# RF08bck.net
KiCad netlist of a schematic drawn in EAGLE
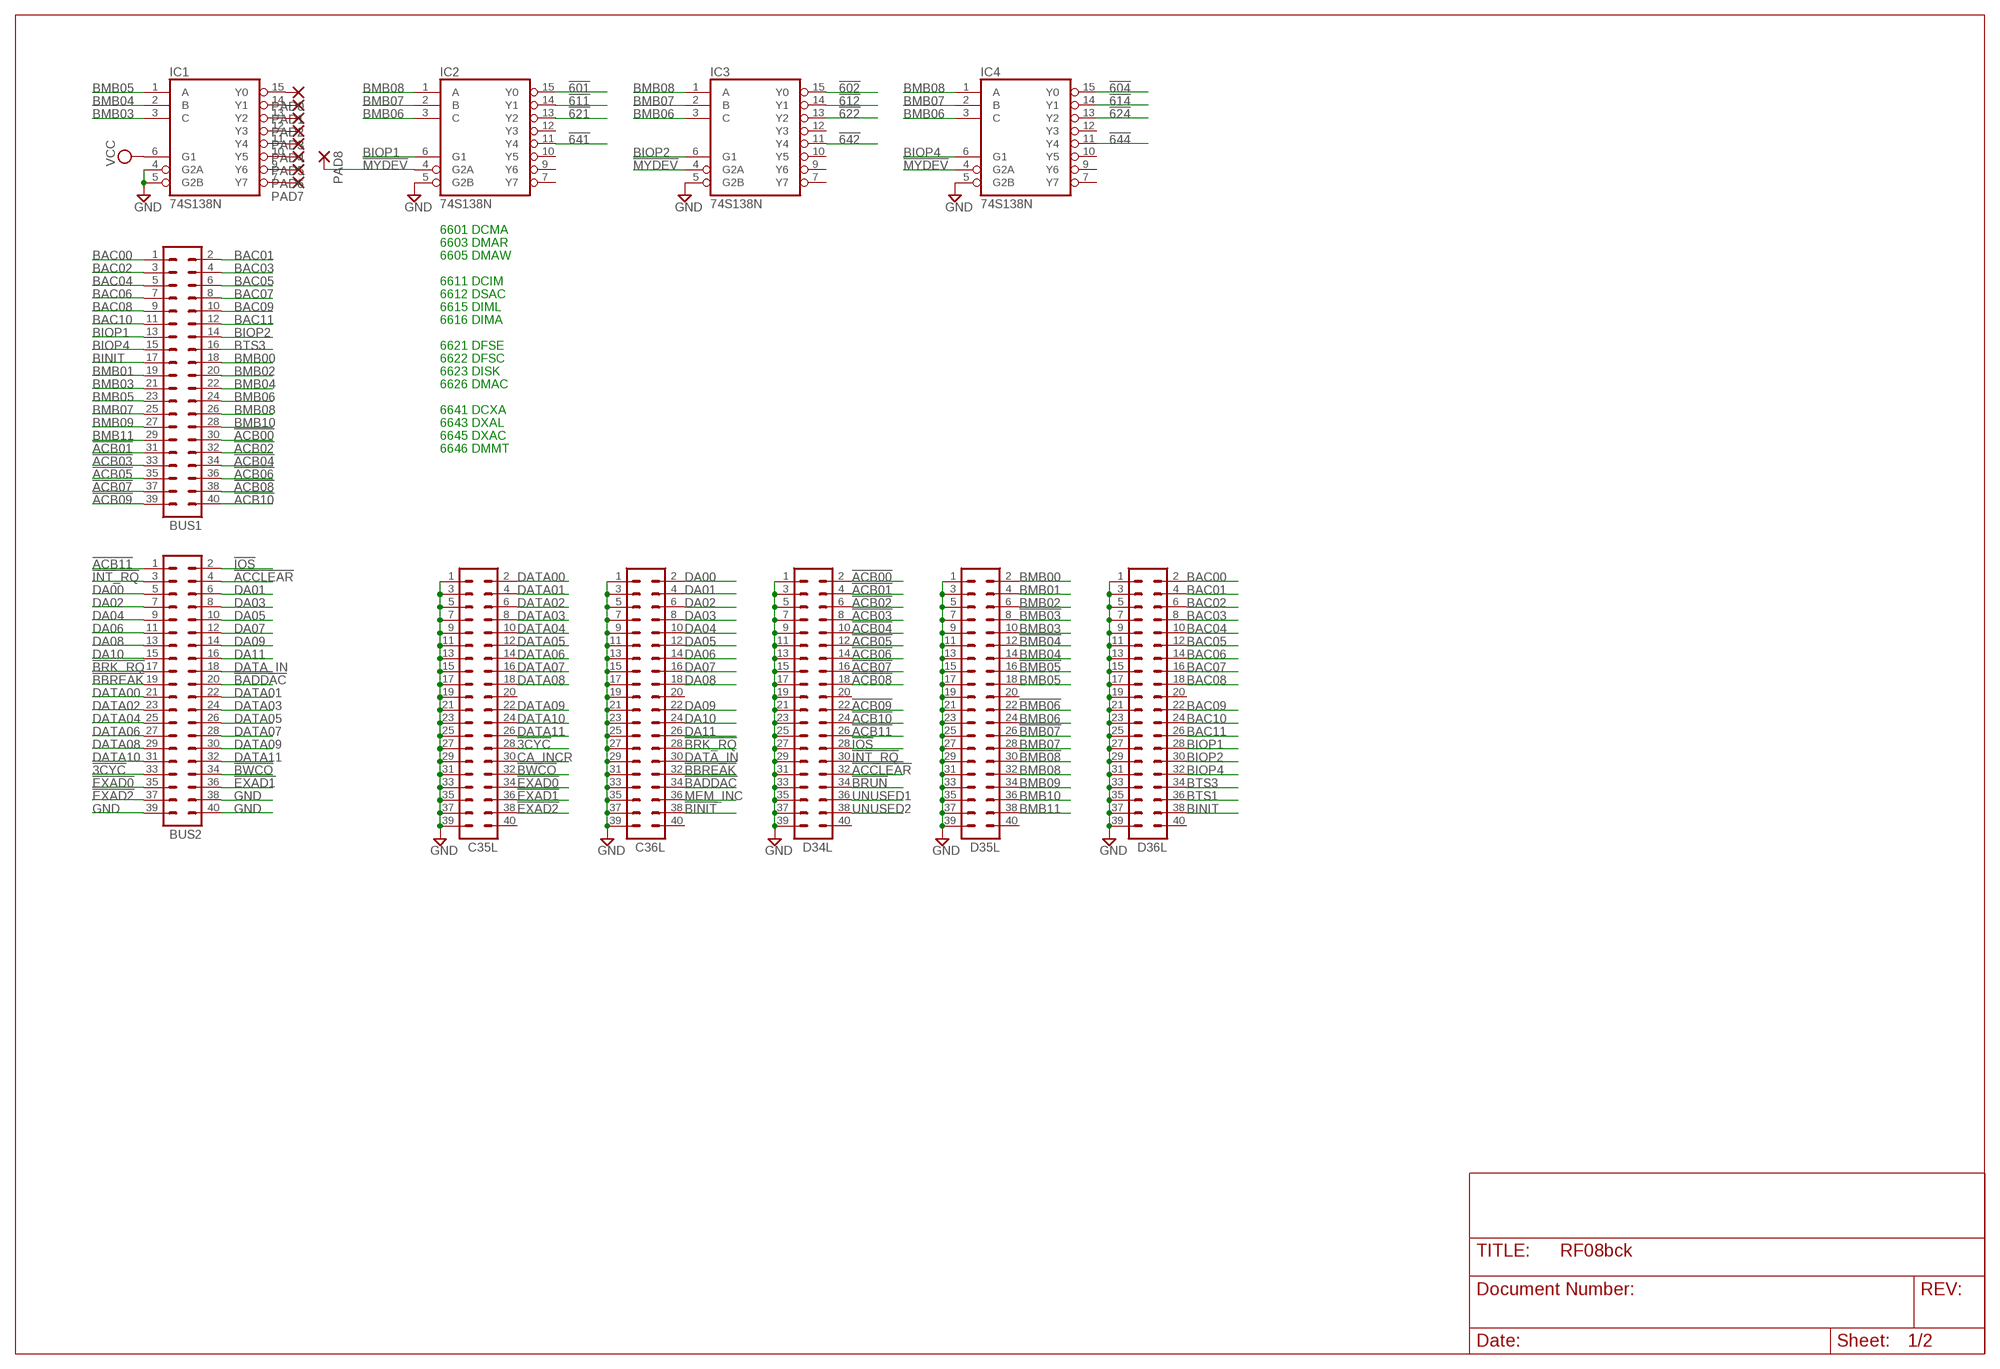
[diagram p0: schematic, sheet 1]
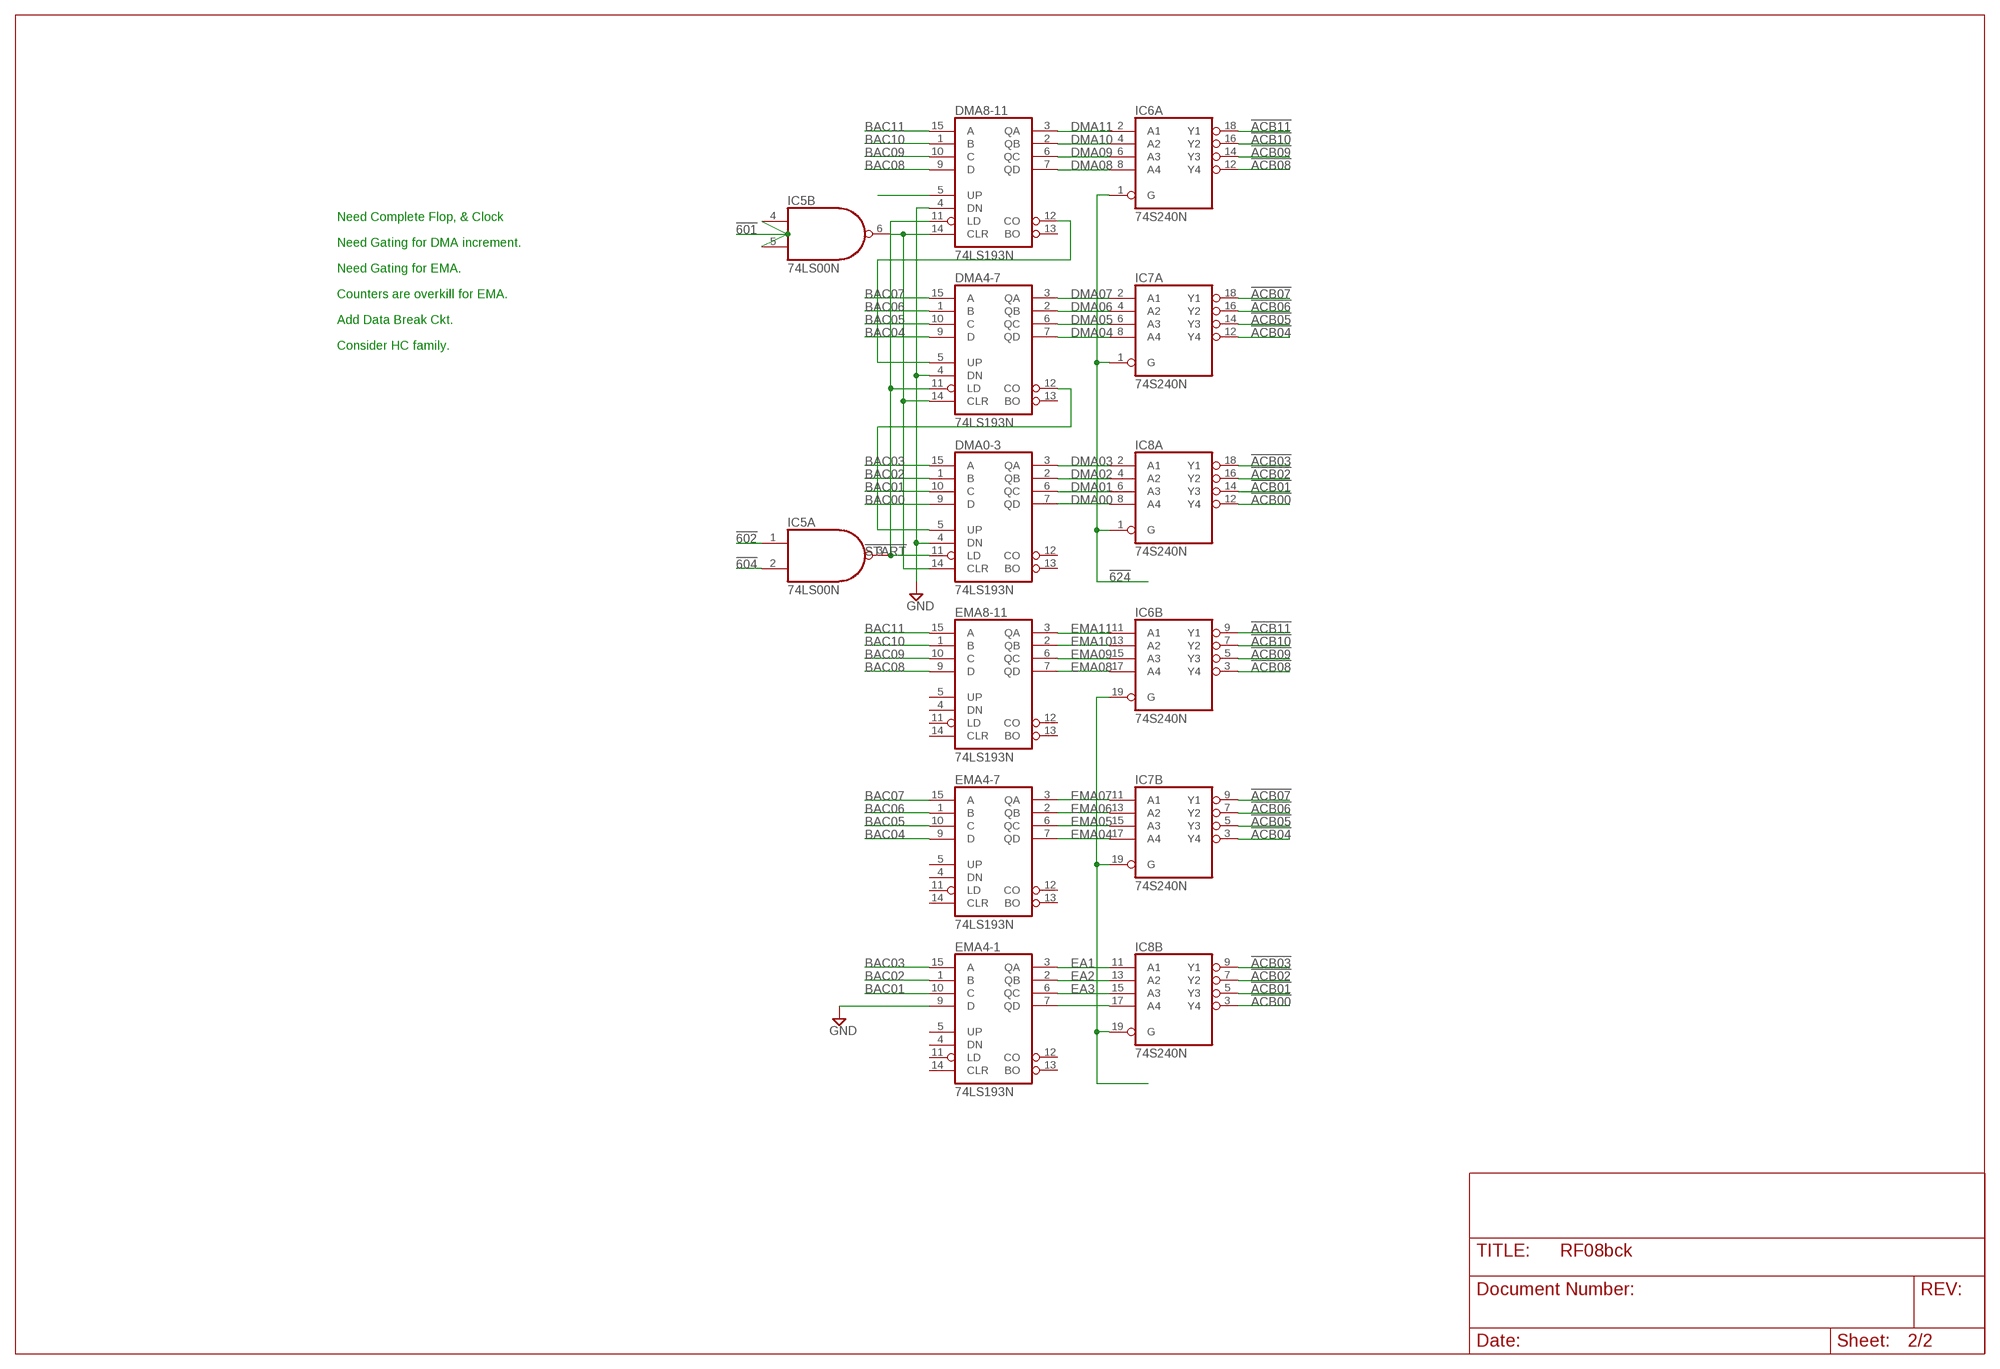
[diagram p1: schematic, sheet 2]

(export (version "E")
  (design (tool "Eeschema 10.0.6"))
  (components
    (comp (ref "DMA0-3")
      (value "74LS193N")
      (footprint "eagle-import:DIL16")
      (libsource (lib "eagle-import") (part "74192NLS"))
    )
    (comp (ref "DMA4-7")
      (value "74LS193N")
      (footprint "eagle-import:DIL16")
      (libsource (lib "eagle-import") (part "74192NLS"))
    )
    (comp (ref "DMA8-11")
      (value "74LS193N")
      (footprint "eagle-import:DIL16")
      (libsource (lib "eagle-import") (part "74192NLS"))
    )
    (comp (ref "EMA4-1")
      (value "74LS193N")
      (footprint "eagle-import:DIL16")
      (libsource (lib "eagle-import") (part "74192NLS"))
    )
    (comp (ref "EMA4-7")
      (value "74LS193N")
      (footprint "eagle-import:DIL16")
      (libsource (lib "eagle-import") (part "74192NLS"))
    )
    (comp (ref "EMA8-11")
      (value "74LS193N")
      (footprint "eagle-import:DIL16")
      (libsource (lib "eagle-import") (part "74192NLS"))
    )
    (comp (ref "IC5")
      (value "74LS00N")
      (footprint "eagle-import:DIL14")
      (libsource (lib "eagle-import") (part "7400NLS"))
    )
    (comp (ref "IC6")
      (value "74S240N")
      (footprint "eagle-import:DIL20")
      (libsource (lib "eagle-import") (part "74240NS"))
    )
    (comp (ref "IC7")
      (value "74S240N")
      (footprint "eagle-import:DIL20")
      (libsource (lib "eagle-import") (part "74240NS"))
    )
    (comp (ref "IC8")
      (value "74S240N")
      (footprint "eagle-import:DIL20")
      (libsource (lib "eagle-import") (part "74240NS"))
    )
    (comp (ref "BUS1")
      (value "MA20-2")
      (footprint "eagle-import:MA20-2")
      (libsource (lib "eagle-import") (part "MA20-2"))
    )
    (comp (ref "BUS2")
      (value "MA20-2")
      (footprint "eagle-import:MA20-2")
      (libsource (lib "eagle-import") (part "MA20-2"))
    )
    (comp (ref "C35L")
      (value "MA20-2")
      (footprint "eagle-import:MA20-2")
      (libsource (lib "eagle-import") (part "MA20-2"))
    )
    (comp (ref "C36L")
      (value "MA20-2")
      (footprint "eagle-import:MA20-2")
      (libsource (lib "eagle-import") (part "MA20-2"))
    )
    (comp (ref "D34L")
      (value "MA20-2")
      (footprint "eagle-import:MA20-2")
      (libsource (lib "eagle-import") (part "MA20-2"))
    )
    (comp (ref "D35L")
      (value "MA20-2")
      (footprint "eagle-import:MA20-2")
      (libsource (lib "eagle-import") (part "MA20-2"))
    )
    (comp (ref "D36L")
      (value "MA20-2")
      (footprint "eagle-import:MA20-2")
      (libsource (lib "eagle-import") (part "MA20-2"))
    )
    (comp (ref "IC1")
      (value "74S138N")
      (footprint "eagle-import:DIL16")
      (libsource (lib "eagle-import") (part "74138NS"))
    )
    (comp (ref "IC2")
      (value "74S138N")
      (footprint "eagle-import:DIL16")
      (libsource (lib "eagle-import") (part "74138NS"))
    )
    (comp (ref "IC3")
      (value "74S138N")
      (footprint "eagle-import:DIL16")
      (libsource (lib "eagle-import") (part "74138NS"))
    )
    (comp (ref "IC4")
      (value "74S138N")
      (footprint "eagle-import:DIL16")
      (libsource (lib "eagle-import") (part "74138NS"))
    )
    (comp (ref "PAD0")
      (value "1,6/0,8")
      (footprint "eagle-import:1,6_0,8")
      (libsource (lib "eagle-import") (part "1,6/0,8"))
    )
    (comp (ref "PAD1")
      (value "1,6/0,8")
      (footprint "eagle-import:1,6_0,8")
      (libsource (lib "eagle-import") (part "1,6/0,8"))
    )
    (comp (ref "PAD2")
      (value "1,6/0,8")
      (footprint "eagle-import:1,6_0,8")
      (libsource (lib "eagle-import") (part "1,6/0,8"))
    )
    (comp (ref "PAD3")
      (value "1,6/0,8")
      (footprint "eagle-import:1,6_0,8")
      (libsource (lib "eagle-import") (part "1,6/0,8"))
    )
    (comp (ref "PAD4")
      (value "1,6/0,8")
      (footprint "eagle-import:1,6_0,8")
      (libsource (lib "eagle-import") (part "1,6/0,8"))
    )
    (comp (ref "PAD5")
      (value "1,6/0,8")
      (footprint "eagle-import:1,6_0,8")
      (libsource (lib "eagle-import") (part "1,6/0,8"))
    )
    (comp (ref "PAD6")
      (value "1,6/0,8")
      (footprint "eagle-import:1,6_0,8")
      (libsource (lib "eagle-import") (part "1,6/0,8"))
    )
    (comp (ref "PAD7")
      (value "1,6/0,8")
      (footprint "eagle-import:1,6_0,8")
      (libsource (lib "eagle-import") (part "1,6/0,8"))
    )
    (comp (ref "PAD8")
      (value "1,6/0,8")
      (footprint "eagle-import:1,6_0,8")
      (libsource (lib "eagle-import") (part "1,6/0,8"))
    )
  )
  (nets
    (net (code "1") (name "BAC00") (class "Default")
      (node (ref "BUS1") (pin "1") (pinfunction "1_1") (pintype "passive"))
      (node (ref "D36L") (pin "2") (pinfunction "2_2") (pintype "passive"))
      (node (ref "DMA0-3") (pin "9") (pinfunction "D_9") (pintype "input"))
    )
    (net (code "2") (name "BAC01") (class "Default")
      (node (ref "BUS1") (pin "2") (pinfunction "2_2") (pintype "passive"))
      (node (ref "D36L") (pin "4") (pinfunction "4_4") (pintype "passive"))
      (node (ref "DMA0-3") (pin "10") (pinfunction "C_10") (pintype "input"))
      (node (ref "EMA4-1") (pin "10") (pinfunction "C_10") (pintype "input"))
    )
    (net (code "3") (name "BAC02") (class "Default")
      (node (ref "BUS1") (pin "3") (pinfunction "3_3") (pintype "passive"))
      (node (ref "D36L") (pin "6") (pinfunction "6_6") (pintype "passive"))
      (node (ref "DMA0-3") (pin "1") (pinfunction "B_1") (pintype "input"))
      (node (ref "EMA4-1") (pin "1") (pinfunction "B_1") (pintype "input"))
    )
    (net (code "4") (name "BAC03") (class "Default")
      (node (ref "BUS1") (pin "4") (pinfunction "4_4") (pintype "passive"))
      (node (ref "D36L") (pin "8") (pinfunction "8_8") (pintype "passive"))
      (node (ref "DMA0-3") (pin "15") (pinfunction "A_15") (pintype "input"))
      (node (ref "EMA4-1") (pin "15") (pinfunction "A_15") (pintype "input"))
    )
    (net (code "5") (name "BAC04") (class "Default")
      (node (ref "BUS1") (pin "5") (pinfunction "5_5") (pintype "passive"))
      (node (ref "D36L") (pin "10") (pinfunction "10_10") (pintype "passive"))
      (node (ref "DMA4-7") (pin "9") (pinfunction "D_9") (pintype "input"))
      (node (ref "EMA4-7") (pin "9") (pinfunction "D_9") (pintype "input"))
    )
    (net (code "6") (name "BAC05") (class "Default")
      (node (ref "BUS1") (pin "6") (pinfunction "6_6") (pintype "passive"))
      (node (ref "D36L") (pin "12") (pinfunction "12_12") (pintype "passive"))
      (node (ref "DMA4-7") (pin "10") (pinfunction "C_10") (pintype "input"))
      (node (ref "EMA4-7") (pin "10") (pinfunction "C_10") (pintype "input"))
    )
    (net (code "7") (name "BAC06") (class "Default")
      (node (ref "BUS1") (pin "7") (pinfunction "7_7") (pintype "passive"))
      (node (ref "D36L") (pin "14") (pinfunction "14_14") (pintype "passive"))
      (node (ref "DMA4-7") (pin "1") (pinfunction "B_1") (pintype "input"))
      (node (ref "EMA4-7") (pin "1") (pinfunction "B_1") (pintype "input"))
    )
    (net (code "8") (name "BAC07") (class "Default")
      (node (ref "BUS1") (pin "8") (pinfunction "8_8") (pintype "passive"))
      (node (ref "D36L") (pin "16") (pinfunction "16_16") (pintype "passive"))
      (node (ref "DMA4-7") (pin "15") (pinfunction "A_15") (pintype "input"))
      (node (ref "EMA4-7") (pin "15") (pinfunction "A_15") (pintype "input"))
    )
    (net (code "9") (name "BAC08") (class "Default")
      (node (ref "BUS1") (pin "9") (pinfunction "9_9") (pintype "passive"))
      (node (ref "D36L") (pin "18") (pinfunction "18_18") (pintype "passive"))
      (node (ref "DMA8-11") (pin "9") (pinfunction "D_9") (pintype "input"))
      (node (ref "EMA8-11") (pin "9") (pinfunction "D_9") (pintype "input"))
    )
    (net (code "10") (name "BAC09") (class "Default")
      (node (ref "BUS1") (pin "10") (pinfunction "10_10") (pintype "passive"))
      (node (ref "D36L") (pin "22") (pinfunction "22_22") (pintype "passive"))
      (node (ref "DMA8-11") (pin "10") (pinfunction "C_10") (pintype "input"))
      (node (ref "EMA8-11") (pin "10") (pinfunction "C_10") (pintype "input"))
    )
    (net (code "11") (name "BAC10") (class "Default")
      (node (ref "BUS1") (pin "11") (pinfunction "11_11") (pintype "passive"))
      (node (ref "D36L") (pin "24") (pinfunction "24_24") (pintype "passive"))
      (node (ref "DMA8-11") (pin "1") (pinfunction "B_1") (pintype "input"))
      (node (ref "EMA8-11") (pin "1") (pinfunction "B_1") (pintype "input"))
    )
    (net (code "12") (name "BAC11") (class "Default")
      (node (ref "BUS1") (pin "12") (pinfunction "12_12") (pintype "passive"))
      (node (ref "D36L") (pin "26") (pinfunction "26_26") (pintype "passive"))
      (node (ref "DMA8-11") (pin "15") (pinfunction "A_15") (pintype "input"))
      (node (ref "EMA8-11") (pin "15") (pinfunction "A_15") (pintype "input"))
    )
    (net (code "13") (name "BINIT") (class "Default")
      (node (ref "BUS1") (pin "17") (pinfunction "17_17") (pintype "passive"))
      (node (ref "D36L") (pin "38") (pinfunction "38_38") (pintype "passive"))
    )
    (net (code "14") (name "BIOP1") (class "Default")
      (node (ref "BUS1") (pin "13") (pinfunction "13_13") (pintype "passive"))
      (node (ref "D36L") (pin "28") (pinfunction "28_28") (pintype "passive"))
      (node (ref "IC2") (pin "6") (pinfunction "G1_6") (pintype "input"))
    )
    (net (code "15") (name "BIOP2") (class "Default")
      (node (ref "BUS1") (pin "14") (pinfunction "14_14") (pintype "passive"))
      (node (ref "D36L") (pin "30") (pinfunction "30_30") (pintype "passive"))
      (node (ref "IC3") (pin "6") (pinfunction "G1_6") (pintype "input"))
    )
    (net (code "16") (name "BIOP4") (class "Default")
      (node (ref "BUS1") (pin "15") (pinfunction "15_15") (pintype "passive"))
      (node (ref "D36L") (pin "32") (pinfunction "32_32") (pintype "passive"))
      (node (ref "IC4") (pin "6") (pinfunction "G1_6") (pintype "input"))
    )
    (net (code "17") (name "BMB00") (class "Default")
      (node (ref "BUS1") (pin "18") (pinfunction "18_18") (pintype "passive"))
      (node (ref "D35L") (pin "2") (pinfunction "2_2") (pintype "passive"))
    )
    (net (code "18") (name "BMB01") (class "Default")
      (node (ref "BUS1") (pin "19") (pinfunction "19_19") (pintype "passive"))
      (node (ref "D35L") (pin "4") (pinfunction "4_4") (pintype "passive"))
    )
    (net (code "19") (name "BMB02") (class "Default")
      (node (ref "BUS1") (pin "20") (pinfunction "20_20") (pintype "passive"))
      (node (ref "D35L") (pin "6") (pinfunction "6_6") (pintype "passive"))
    )
    (net (code "20") (name "BMB03") (class "Default")
      (node (ref "BUS1") (pin "21") (pinfunction "21_21") (pintype "passive"))
      (node (ref "D35L") (pin "10") (pinfunction "10_10") (pintype "passive"))
      (node (ref "IC1") (pin "3") (pinfunction "C_3") (pintype "input"))
    )
    (net (code "21") (name "BMB04") (class "Default")
      (node (ref "BUS1") (pin "22") (pinfunction "22_22") (pintype "passive"))
      (node (ref "D35L") (pin "14") (pinfunction "14_14") (pintype "passive"))
      (node (ref "IC1") (pin "2") (pinfunction "B_2") (pintype "input"))
    )
    (net (code "22") (name "BMB05") (class "Default")
      (node (ref "BUS1") (pin "23") (pinfunction "23_23") (pintype "passive"))
      (node (ref "D35L") (pin "18") (pinfunction "18_18") (pintype "passive"))
      (node (ref "IC1") (pin "1") (pinfunction "A_1") (pintype "input"))
    )
    (net (code "23") (name "BMB06") (class "Default")
      (node (ref "BUS1") (pin "24") (pinfunction "24_24") (pintype "passive"))
      (node (ref "D35L") (pin "24") (pinfunction "24_24") (pintype "passive"))
      (node (ref "IC2") (pin "3") (pinfunction "C_3") (pintype "input"))
      (node (ref "IC3") (pin "3") (pinfunction "C_3") (pintype "input"))
      (node (ref "IC4") (pin "3") (pinfunction "C_3") (pintype "input"))
    )
    (net (code "24") (name "BMB07") (class "Default")
      (node (ref "BUS1") (pin "25") (pinfunction "25_25") (pintype "passive"))
      (node (ref "D35L") (pin "28") (pinfunction "28_28") (pintype "passive"))
      (node (ref "IC2") (pin "2") (pinfunction "B_2") (pintype "input"))
      (node (ref "IC3") (pin "2") (pinfunction "B_2") (pintype "input"))
      (node (ref "IC4") (pin "2") (pinfunction "B_2") (pintype "input"))
    )
    (net (code "25") (name "BMB08") (class "Default")
      (node (ref "BUS1") (pin "26") (pinfunction "26_26") (pintype "passive"))
      (node (ref "D35L") (pin "32") (pinfunction "32_32") (pintype "passive"))
      (node (ref "IC2") (pin "1") (pinfunction "A_1") (pintype "input"))
      (node (ref "IC3") (pin "1") (pinfunction "A_1") (pintype "input"))
      (node (ref "IC4") (pin "1") (pinfunction "A_1") (pintype "input"))
    )
    (net (code "26") (name "BMB09") (class "Default")
      (node (ref "BUS1") (pin "27") (pinfunction "27_27") (pintype "passive"))
      (node (ref "D35L") (pin "34") (pinfunction "34_34") (pintype "passive"))
    )
    (net (code "27") (name "BMB10") (class "Default")
      (node (ref "BUS1") (pin "28") (pinfunction "28_28") (pintype "passive"))
      (node (ref "D35L") (pin "36") (pinfunction "36_36") (pintype "passive"))
    )
    (net (code "28") (name "BMB11") (class "Default")
      (node (ref "BUS1") (pin "29") (pinfunction "29_29") (pintype "passive"))
      (node (ref "D35L") (pin "38") (pinfunction "38_38") (pintype "passive"))
    )
    (net (code "29") (name "BTS1") (class "Default")
      (node (ref "D36L") (pin "36") (pinfunction "36_36") (pintype "passive"))
    )
    (net (code "30") (name "BTS3") (class "Default")
      (node (ref "BUS1") (pin "16") (pinfunction "16_16") (pintype "passive"))
      (node (ref "D36L") (pin "34") (pinfunction "34_34") (pintype "passive"))
    )
    (net (code "31") (name "CA_INCR") (class "Default")
      (node (ref "C35L") (pin "30") (pinfunction "30_30") (pintype "passive"))
    )
    (net (code "32") (name "DA00") (class "Default")
      (node (ref "BUS2") (pin "5") (pinfunction "5_5") (pintype "passive"))
      (node (ref "C36L") (pin "2") (pinfunction "2_2") (pintype "passive"))
    )
    (net (code "33") (name "DA01") (class "Default")
      (node (ref "BUS2") (pin "6") (pinfunction "6_6") (pintype "passive"))
      (node (ref "C36L") (pin "4") (pinfunction "4_4") (pintype "passive"))
    )
    (net (code "34") (name "DA02") (class "Default")
      (node (ref "BUS2") (pin "7") (pinfunction "7_7") (pintype "passive"))
      (node (ref "C36L") (pin "6") (pinfunction "6_6") (pintype "passive"))
    )
    (net (code "35") (name "DA03") (class "Default")
      (node (ref "BUS2") (pin "8") (pinfunction "8_8") (pintype "passive"))
      (node (ref "C36L") (pin "8") (pinfunction "8_8") (pintype "passive"))
    )
    (net (code "36") (name "DA04") (class "Default")
      (node (ref "BUS2") (pin "9") (pinfunction "9_9") (pintype "passive"))
      (node (ref "C36L") (pin "10") (pinfunction "10_10") (pintype "passive"))
    )
    (net (code "37") (name "DA05") (class "Default")
      (node (ref "BUS2") (pin "10") (pinfunction "10_10") (pintype "passive"))
      (node (ref "C36L") (pin "12") (pinfunction "12_12") (pintype "passive"))
    )
    (net (code "38") (name "DA06") (class "Default")
      (node (ref "BUS2") (pin "11") (pinfunction "11_11") (pintype "passive"))
      (node (ref "C36L") (pin "14") (pinfunction "14_14") (pintype "passive"))
    )
    (net (code "39") (name "DA07") (class "Default")
      (node (ref "BUS2") (pin "12") (pinfunction "12_12") (pintype "passive"))
      (node (ref "C36L") (pin "16") (pinfunction "16_16") (pintype "passive"))
    )
    (net (code "40") (name "DA08") (class "Default")
      (node (ref "BUS2") (pin "13") (pinfunction "13_13") (pintype "passive"))
      (node (ref "C36L") (pin "18") (pinfunction "18_18") (pintype "passive"))
    )
    (net (code "41") (name "DA09") (class "Default")
      (node (ref "BUS2") (pin "14") (pinfunction "14_14") (pintype "passive"))
      (node (ref "C36L") (pin "22") (pinfunction "22_22") (pintype "passive"))
    )
    (net (code "42") (name "DA10") (class "Default")
      (node (ref "BUS2") (pin "15") (pinfunction "15_15") (pintype "passive"))
      (node (ref "C36L") (pin "24") (pinfunction "24_24") (pintype "passive"))
    )
    (net (code "43") (name "DA11") (class "Default")
      (node (ref "BUS2") (pin "16") (pinfunction "16_16") (pintype "passive"))
      (node (ref "C36L") (pin "26") (pinfunction "26_26") (pintype "passive"))
    )
    (net (code "44") (name "DATA00") (class "Default")
      (node (ref "BUS2") (pin "21") (pinfunction "21_21") (pintype "passive"))
      (node (ref "C35L") (pin "2") (pinfunction "2_2") (pintype "passive"))
    )
    (net (code "45") (name "DATA01") (class "Default")
      (node (ref "BUS2") (pin "22") (pinfunction "22_22") (pintype "passive"))
      (node (ref "C35L") (pin "4") (pinfunction "4_4") (pintype "passive"))
    )
    (net (code "46") (name "DATA02") (class "Default")
      (node (ref "BUS2") (pin "23") (pinfunction "23_23") (pintype "passive"))
      (node (ref "C35L") (pin "6") (pinfunction "6_6") (pintype "passive"))
    )
    (net (code "47") (name "DATA03") (class "Default")
      (node (ref "BUS2") (pin "24") (pinfunction "24_24") (pintype "passive"))
      (node (ref "C35L") (pin "8") (pinfunction "8_8") (pintype "passive"))
    )
    (net (code "48") (name "DATA04") (class "Default")
      (node (ref "BUS2") (pin "25") (pinfunction "25_25") (pintype "passive"))
      (node (ref "C35L") (pin "10") (pinfunction "10_10") (pintype "passive"))
    )
    (net (code "49") (name "DATA05") (class "Default")
      (node (ref "BUS2") (pin "26") (pinfunction "26_26") (pintype "passive"))
      (node (ref "C35L") (pin "12") (pinfunction "12_12") (pintype "passive"))
    )
    (net (code "50") (name "DATA06") (class "Default")
      (node (ref "BUS2") (pin "27") (pinfunction "27_27") (pintype "passive"))
      (node (ref "C35L") (pin "14") (pinfunction "14_14") (pintype "passive"))
    )
    (net (code "51") (name "DATA07") (class "Default")
      (node (ref "BUS2") (pin "28") (pinfunction "28_28") (pintype "passive"))
      (node (ref "C35L") (pin "16") (pinfunction "16_16") (pintype "passive"))
    )
    (net (code "52") (name "DATA08") (class "Default")
      (node (ref "BUS2") (pin "29") (pinfunction "29_29") (pintype "passive"))
      (node (ref "C35L") (pin "18") (pinfunction "18_18") (pintype "passive"))
    )
    (net (code "53") (name "DATA09") (class "Default")
      (node (ref "BUS2") (pin "30") (pinfunction "30_30") (pintype "passive"))
      (node (ref "C35L") (pin "22") (pinfunction "22_22") (pintype "passive"))
    )
    (net (code "54") (name "DATA10") (class "Default")
      (node (ref "BUS2") (pin "31") (pinfunction "31_31") (pintype "passive"))
      (node (ref "C35L") (pin "24") (pinfunction "24_24") (pintype "passive"))
    )
    (net (code "55") (name "DATA11") (class "Default")
      (node (ref "BUS2") (pin "32") (pinfunction "32_32") (pintype "passive"))
      (node (ref "C35L") (pin "26") (pinfunction "26_26") (pintype "passive"))
    )
    (net (code "56") (name "DATA_IN") (class "Default")
      (node (ref "BUS2") (pin "18") (pinfunction "18_18") (pintype "passive"))
      (node (ref "C36L") (pin "30") (pinfunction "30_30") (pintype "passive"))
    )
    (net (code "57") (name "DMA00") (class "Default")
      (node (ref "DMA0-3") (pin "7") (pinfunction "QD_7") (pintype "output"))
      (node (ref "IC8") (pin "8") (pinfunction "A4_8") (pintype "input"))
    )
    (net (code "58") (name "DMA01") (class "Default")
      (node (ref "DMA0-3") (pin "6") (pinfunction "QC_6") (pintype "output"))
      (node (ref "IC8") (pin "6") (pinfunction "A3_6") (pintype "input"))
    )
    (net (code "59") (name "DMA02") (class "Default")
      (node (ref "DMA0-3") (pin "2") (pinfunction "QB_2") (pintype "output"))
      (node (ref "IC8") (pin "4") (pinfunction "A2_4") (pintype "input"))
    )
    (net (code "60") (name "DMA03") (class "Default")
      (node (ref "DMA0-3") (pin "3") (pinfunction "QA_3") (pintype "output"))
      (node (ref "IC8") (pin "2") (pinfunction "A1_2") (pintype "input"))
    )
    (net (code "61") (name "DMA04") (class "Default")
      (node (ref "DMA4-7") (pin "7") (pinfunction "QD_7") (pintype "output"))
      (node (ref "IC7") (pin "8") (pinfunction "A4_8") (pintype "input"))
    )
    (net (code "62") (name "DMA05") (class "Default")
      (node (ref "DMA4-7") (pin "6") (pinfunction "QC_6") (pintype "output"))
      (node (ref "IC7") (pin "6") (pinfunction "A3_6") (pintype "input"))
    )
    (net (code "63") (name "DMA06") (class "Default")
      (node (ref "DMA4-7") (pin "2") (pinfunction "QB_2") (pintype "output"))
      (node (ref "IC7") (pin "4") (pinfunction "A2_4") (pintype "input"))
    )
    (net (code "64") (name "DMA07") (class "Default")
      (node (ref "DMA4-7") (pin "3") (pinfunction "QA_3") (pintype "output"))
      (node (ref "IC7") (pin "2") (pinfunction "A1_2") (pintype "input"))
    )
    (net (code "65") (name "DMA08") (class "Default")
      (node (ref "DMA8-11") (pin "7") (pinfunction "QD_7") (pintype "output"))
      (node (ref "IC6") (pin "8") (pinfunction "A4_8") (pintype "input"))
    )
    (net (code "66") (name "DMA09") (class "Default")
      (node (ref "DMA8-11") (pin "6") (pinfunction "QC_6") (pintype "output"))
      (node (ref "IC6") (pin "6") (pinfunction "A3_6") (pintype "input"))
    )
    (net (code "67") (name "DMA10") (class "Default")
      (node (ref "DMA8-11") (pin "2") (pinfunction "QB_2") (pintype "output"))
      (node (ref "IC6") (pin "4") (pinfunction "A2_4") (pintype "input"))
    )
    (net (code "68") (name "DMA11") (class "Default")
      (node (ref "DMA8-11") (pin "3") (pinfunction "QA_3") (pintype "output"))
      (node (ref "IC6") (pin "2") (pinfunction "A1_2") (pintype "input"))
    )
    (net (code "69") (name "EA1") (class "Default")
      (node (ref "EMA4-1") (pin "3") (pinfunction "QA_3") (pintype "output"))
      (node (ref "IC8") (pin "11") (pinfunction "A1_11") (pintype "input"))
    )
    (net (code "70") (name "EA2") (class "Default")
      (node (ref "EMA4-1") (pin "2") (pinfunction "QB_2") (pintype "output"))
      (node (ref "IC8") (pin "13") (pinfunction "A2_13") (pintype "input"))
    )
    (net (code "71") (name "EA3") (class "Default")
      (node (ref "EMA4-1") (pin "6") (pinfunction "QC_6") (pintype "output"))
      (node (ref "IC8") (pin "15") (pinfunction "A3_15") (pintype "input"))
    )
    (net (code "72") (name "EMA04") (class "Default")
      (node (ref "EMA4-7") (pin "7") (pinfunction "QD_7") (pintype "output"))
      (node (ref "IC7") (pin "17") (pinfunction "A4_17") (pintype "input"))
    )
    (net (code "73") (name "EMA05") (class "Default")
      (node (ref "EMA4-7") (pin "6") (pinfunction "QC_6") (pintype "output"))
      (node (ref "IC7") (pin "15") (pinfunction "A3_15") (pintype "input"))
    )
    (net (code "74") (name "EMA06") (class "Default")
      (node (ref "EMA4-7") (pin "2") (pinfunction "QB_2") (pintype "output"))
      (node (ref "IC7") (pin "13") (pinfunction "A2_13") (pintype "input"))
    )
    (net (code "75") (name "EMA07") (class "Default")
      (node (ref "EMA4-7") (pin "3") (pinfunction "QA_3") (pintype "output"))
      (node (ref "IC7") (pin "11") (pinfunction "A1_11") (pintype "input"))
    )
    (net (code "76") (name "EMA08") (class "Default")
      (node (ref "EMA8-11") (pin "7") (pinfunction "QD_7") (pintype "output"))
      (node (ref "IC6") (pin "17") (pinfunction "A4_17") (pintype "input"))
    )
    (net (code "77") (name "EMA09") (class "Default")
      (node (ref "EMA8-11") (pin "6") (pinfunction "QC_6") (pintype "output"))
      (node (ref "IC6") (pin "15") (pinfunction "A3_15") (pintype "input"))
    )
    (net (code "78") (name "EMA10") (class "Default")
      (node (ref "EMA8-11") (pin "2") (pinfunction "QB_2") (pintype "output"))
      (node (ref "IC6") (pin "13") (pinfunction "A2_13") (pintype "input"))
    )
    (net (code "79") (name "EMA11") (class "Default")
      (node (ref "EMA8-11") (pin "3") (pinfunction "QA_3") (pintype "output"))
      (node (ref "IC6") (pin "11") (pinfunction "A1_11") (pintype "input"))
    )
    (net (code "80") (name "GND") (class "Default")
      (node (ref "BUS2") (pin "38") (pinfunction "38_38") (pintype "passive"))
      (node (ref "BUS2") (pin "39") (pinfunction "39_39") (pintype "passive"))
      (node (ref "BUS2") (pin "40") (pinfunction "40_40") (pintype "passive"))
      (node (ref "C35L") (pin "1") (pinfunction "1_1") (pintype "passive"))
      (node (ref "C35L") (pin "11") (pinfunction "11_11") (pintype "passive"))
      (node (ref "C35L") (pin "13") (pinfunction "13_13") (pintype "passive"))
      (node (ref "C35L") (pin "15") (pinfunction "15_15") (pintype "passive"))
      (node (ref "C35L") (pin "17") (pinfunction "17_17") (pintype "passive"))
      (node (ref "C35L") (pin "19") (pinfunction "19_19") (pintype "passive"))
      (node (ref "C35L") (pin "21") (pinfunction "21_21") (pintype "passive"))
      (node (ref "C35L") (pin "23") (pinfunction "23_23") (pintype "passive"))
      (node (ref "C35L") (pin "25") (pinfunction "25_25") (pintype "passive"))
      (node (ref "C35L") (pin "27") (pinfunction "27_27") (pintype "passive"))
      (node (ref "C35L") (pin "29") (pinfunction "29_29") (pintype "passive"))
      (node (ref "C35L") (pin "3") (pinfunction "3_3") (pintype "passive"))
      (node (ref "C35L") (pin "31") (pinfunction "31_31") (pintype "passive"))
      (node (ref "C35L") (pin "33") (pinfunction "33_33") (pintype "passive"))
      (node (ref "C35L") (pin "35") (pinfunction "35_35") (pintype "passive"))
      (node (ref "C35L") (pin "37") (pinfunction "37_37") (pintype "passive"))
      (node (ref "C35L") (pin "39") (pinfunction "39_39") (pintype "passive"))
      (node (ref "C35L") (pin "5") (pinfunction "5_5") (pintype "passive"))
      (node (ref "C35L") (pin "7") (pinfunction "7_7") (pintype "passive"))
      (node (ref "C35L") (pin "9") (pinfunction "9_9") (pintype "passive"))
      (node (ref "C36L") (pin "1") (pinfunction "1_1") (pintype "passive"))
      (node (ref "C36L") (pin "11") (pinfunction "11_11") (pintype "passive"))
      (node (ref "C36L") (pin "13") (pinfunction "13_13") (pintype "passive"))
      (node (ref "C36L") (pin "15") (pinfunction "15_15") (pintype "passive"))
      (node (ref "C36L") (pin "17") (pinfunction "17_17") (pintype "passive"))
      (node (ref "C36L") (pin "19") (pinfunction "19_19") (pintype "passive"))
      (node (ref "C36L") (pin "21") (pinfunction "21_21") (pintype "passive"))
      (node (ref "C36L") (pin "23") (pinfunction "23_23") (pintype "passive"))
      (node (ref "C36L") (pin "25") (pinfunction "25_25") (pintype "passive"))
      (node (ref "C36L") (pin "27") (pinfunction "27_27") (pintype "passive"))
      (node (ref "C36L") (pin "29") (pinfunction "29_29") (pintype "passive"))
      (node (ref "C36L") (pin "3") (pinfunction "3_3") (pintype "passive"))
      (node (ref "C36L") (pin "31") (pinfunction "31_31") (pintype "passive"))
      (node (ref "C36L") (pin "33") (pinfunction "33_33") (pintype "passive"))
      (node (ref "C36L") (pin "35") (pinfunction "35_35") (pintype "passive"))
      (node (ref "C36L") (pin "37") (pinfunction "37_37") (pintype "passive"))
      (node (ref "C36L") (pin "39") (pinfunction "39_39") (pintype "passive"))
      (node (ref "C36L") (pin "5") (pinfunction "5_5") (pintype "passive"))
      (node (ref "C36L") (pin "7") (pinfunction "7_7") (pintype "passive"))
      (node (ref "C36L") (pin "9") (pinfunction "9_9") (pintype "passive"))
      (node (ref "D34L") (pin "1") (pinfunction "1_1") (pintype "passive"))
      (node (ref "D34L") (pin "11") (pinfunction "11_11") (pintype "passive"))
      (node (ref "D34L") (pin "13") (pinfunction "13_13") (pintype "passive"))
      (node (ref "D34L") (pin "15") (pinfunction "15_15") (pintype "passive"))
      (node (ref "D34L") (pin "17") (pinfunction "17_17") (pintype "passive"))
      (node (ref "D34L") (pin "19") (pinfunction "19_19") (pintype "passive"))
      (node (ref "D34L") (pin "21") (pinfunction "21_21") (pintype "passive"))
      (node (ref "D34L") (pin "23") (pinfunction "23_23") (pintype "passive"))
      (node (ref "D34L") (pin "25") (pinfunction "25_25") (pintype "passive"))
      (node (ref "D34L") (pin "27") (pinfunction "27_27") (pintype "passive"))
      (node (ref "D34L") (pin "29") (pinfunction "29_29") (pintype "passive"))
      (node (ref "D34L") (pin "3") (pinfunction "3_3") (pintype "passive"))
      (node (ref "D34L") (pin "31") (pinfunction "31_31") (pintype "passive"))
      (node (ref "D34L") (pin "33") (pinfunction "33_33") (pintype "passive"))
      (node (ref "D34L") (pin "35") (pinfunction "35_35") (pintype "passive"))
      (node (ref "D34L") (pin "37") (pinfunction "37_37") (pintype "passive"))
      (node (ref "D34L") (pin "39") (pinfunction "39_39") (pintype "passive"))
      (node (ref "D34L") (pin "5") (pinfunction "5_5") (pintype "passive"))
      (node (ref "D34L") (pin "7") (pinfunction "7_7") (pintype "passive"))
      (node (ref "D34L") (pin "9") (pinfunction "9_9") (pintype "passive"))
      (node (ref "D35L") (pin "1") (pinfunction "1_1") (pintype "passive"))
      (node (ref "D35L") (pin "11") (pinfunction "11_11") (pintype "passive"))
      (node (ref "D35L") (pin "13") (pinfunction "13_13") (pintype "passive"))
      (node (ref "D35L") (pin "15") (pinfunction "15_15") (pintype "passive"))
      (node (ref "D35L") (pin "17") (pinfunction "17_17") (pintype "passive"))
      (node (ref "D35L") (pin "19") (pinfunction "19_19") (pintype "passive"))
      (node (ref "D35L") (pin "21") (pinfunction "21_21") (pintype "passive"))
      (node (ref "D35L") (pin "23") (pinfunction "23_23") (pintype "passive"))
      (node (ref "D35L") (pin "25") (pinfunction "25_25") (pintype "passive"))
      (node (ref "D35L") (pin "27") (pinfunction "27_27") (pintype "passive"))
      (node (ref "D35L") (pin "29") (pinfunction "29_29") (pintype "passive"))
      (node (ref "D35L") (pin "3") (pinfunction "3_3") (pintype "passive"))
      (node (ref "D35L") (pin "31") (pinfunction "31_31") (pintype "passive"))
      (node (ref "D35L") (pin "33") (pinfunction "33_33") (pintype "passive"))
      (node (ref "D35L") (pin "35") (pinfunction "35_35") (pintype "passive"))
      (node (ref "D35L") (pin "37") (pinfunction "37_37") (pintype "passive"))
      (node (ref "D35L") (pin "39") (pinfunction "39_39") (pintype "passive"))
      (node (ref "D35L") (pin "5") (pinfunction "5_5") (pintype "passive"))
      (node (ref "D35L") (pin "7") (pinfunction "7_7") (pintype "passive"))
      (node (ref "D35L") (pin "9") (pinfunction "9_9") (pintype "passive"))
      (node (ref "D36L") (pin "1") (pinfunction "1_1") (pintype "passive"))
      (node (ref "D36L") (pin "11") (pinfunction "11_11") (pintype "passive"))
      (node (ref "D36L") (pin "13") (pinfunction "13_13") (pintype "passive"))
      (node (ref "D36L") (pin "15") (pinfunction "15_15") (pintype "passive"))
      (node (ref "D36L") (pin "17") (pinfunction "17_17") (pintype "passive"))
      (node (ref "D36L") (pin "19") (pinfunction "19_19") (pintype "passive"))
      (node (ref "D36L") (pin "21") (pinfunction "21_21") (pintype "passive"))
      (node (ref "D36L") (pin "23") (pinfunction "23_23") (pintype "passive"))
      (node (ref "D36L") (pin "25") (pinfunction "25_25") (pintype "passive"))
      (node (ref "D36L") (pin "27") (pinfunction "27_27") (pintype "passive"))
      (node (ref "D36L") (pin "29") (pinfunction "29_29") (pintype "passive"))
      (node (ref "D36L") (pin "3") (pinfunction "3_3") (pintype "passive"))
      (node (ref "D36L") (pin "31") (pinfunction "31_31") (pintype "passive"))
      (node (ref "D36L") (pin "33") (pinfunction "33_33") (pintype "passive"))
      (node (ref "D36L") (pin "35") (pinfunction "35_35") (pintype "passive"))
      (node (ref "D36L") (pin "37") (pinfunction "37_37") (pintype "passive"))
      (node (ref "D36L") (pin "39") (pinfunction "39_39") (pintype "passive"))
      (node (ref "D36L") (pin "5") (pinfunction "5_5") (pintype "passive"))
      (node (ref "D36L") (pin "7") (pinfunction "7_7") (pintype "passive"))
      (node (ref "D36L") (pin "9") (pinfunction "9_9") (pintype "passive"))
      (node (ref "DMA0-3") (pin "4") (pinfunction "DN_4") (pintype "input"))
      (node (ref "DMA4-7") (pin "4") (pinfunction "DN_4") (pintype "input"))
      (node (ref "DMA8-11") (pin "4") (pinfunction "DN_4") (pintype "input"))
      (node (ref "EMA4-1") (pin "9") (pinfunction "D_9") (pintype "input"))
      (node (ref "IC1") (pin "4") (pinfunction "G2A_4") (pintype "input"))
      (node (ref "IC1") (pin "5") (pinfunction "G2B_5") (pintype "input"))
      (node (ref "IC2") (pin "5") (pinfunction "G2B_5") (pintype "input"))
      (node (ref "IC3") (pin "5") (pinfunction "G2B_5") (pintype "input"))
      (node (ref "IC4") (pin "5") (pinfunction "G2B_5") (pintype "input"))
    )
    (net (code "81") (name "MEM_INC") (class "Default")
      (node (ref "C36L") (pin "36") (pinfunction "36_36") (pintype "passive"))
    )
    (net (code "82") (name "Net-(DMA0-3A-CLR)") (class "Default")
      (node (ref "DMA0-3") (pin "14") (pinfunction "CLR_14") (pintype "input"))
      (node (ref "DMA4-7") (pin "14") (pinfunction "CLR_14") (pintype "input"))
      (node (ref "DMA8-11") (pin "14") (pinfunction "CLR_14") (pintype "input"))
      (node (ref "IC5") (pin "6") (pinfunction "O_6") (pintype "output"))
    )
    (net (code "83") (name "Net-(DMA0-3A-UP)") (class "Default")
      (node (ref "DMA0-3") (pin "5") (pinfunction "UP_5") (pintype "input"))
      (node (ref "DMA4-7") (pin "12") (pinfunction "CO_12") (pintype "output"))
    )
    (net (code "84") (name "Net-(DMA4-7A-UP)") (class "Default")
      (node (ref "DMA4-7") (pin "5") (pinfunction "UP_5") (pintype "input"))
      (node (ref "DMA8-11") (pin "12") (pinfunction "CO_12") (pintype "output"))
    )
    (net (code "85") (name "Net-(EMA4-1A-QD)") (class "Default")
      (node (ref "EMA4-1") (pin "7") (pinfunction "QD_7") (pintype "output"))
      (node (ref "IC8") (pin "17") (pinfunction "A4_17") (pintype "input"))
    )
    (net (code "86") (name "Net-(IC1A-Y0)") (class "Default")
      (node (ref "IC1") (pin "15") (pinfunction "Y0_15") (pintype "output"))
      (node (ref "PAD0") (pin "1") (pinfunction "P_1") (pintype "passive"))
    )
    (net (code "87") (name "Net-(IC1A-Y1)") (class "Default")
      (node (ref "IC1") (pin "14") (pinfunction "Y1_14") (pintype "output"))
      (node (ref "PAD1") (pin "1") (pinfunction "P_1") (pintype "passive"))
    )
    (net (code "88") (name "Net-(IC1A-Y2)") (class "Default")
      (node (ref "IC1") (pin "13") (pinfunction "Y2_13") (pintype "output"))
      (node (ref "PAD2") (pin "1") (pinfunction "P_1") (pintype "passive"))
    )
    (net (code "89") (name "Net-(IC1A-Y3)") (class "Default")
      (node (ref "IC1") (pin "12") (pinfunction "Y3_12") (pintype "output"))
      (node (ref "PAD3") (pin "1") (pinfunction "P_1") (pintype "passive"))
    )
    (net (code "90") (name "Net-(IC1A-Y4)") (class "Default")
      (node (ref "IC1") (pin "11") (pinfunction "Y4_11") (pintype "output"))
      (node (ref "PAD4") (pin "1") (pinfunction "P_1") (pintype "passive"))
    )
    (net (code "91") (name "Net-(IC1A-Y5)") (class "Default")
      (node (ref "IC1") (pin "10") (pinfunction "Y5_10") (pintype "output"))
      (node (ref "PAD5") (pin "1") (pinfunction "P_1") (pintype "passive"))
    )
    (net (code "92") (name "Net-(IC1A-Y6)") (class "Default")
      (node (ref "IC1") (pin "9") (pinfunction "Y6_9") (pintype "output"))
      (node (ref "PAD6") (pin "1") (pinfunction "P_1") (pintype "passive"))
    )
    (net (code "93") (name "Net-(IC1A-Y7)") (class "Default")
      (node (ref "IC1") (pin "7") (pinfunction "Y7_7") (pintype "output"))
      (node (ref "PAD7") (pin "1") (pinfunction "P_1") (pintype "passive"))
    )
    (net (code "94") (name "Net-(IC6B-G)") (class "Default")
      (node (ref "IC6") (pin "19") (pinfunction "G_19") (pintype "input"))
      (node (ref "IC7") (pin "19") (pinfunction "G_19") (pintype "input"))
      (node (ref "IC8") (pin "19") (pinfunction "G_19") (pintype "input"))
    )
    (net (code "95") (name "UNUSED1") (class "Default")
      (node (ref "D34L") (pin "36") (pinfunction "36_36") (pintype "passive"))
    )
    (net (code "96") (name "UNUSED2") (class "Default")
      (node (ref "D34L") (pin "38") (pinfunction "38_38") (pintype "passive"))
    )
    (net (code "97") (name "VCC") (class "Default")
      (node (ref "IC1") (pin "6") (pinfunction "G1_6") (pintype "input"))
    )
    (net (code "98") (name "unconnected-(C35L-Pad20)") (class "Default")
      (node (ref "C35L") (pin "20") (pinfunction "20_20") (pintype "passive"))
    )
    (net (code "99") (name "unconnected-(C35L-Pad40)") (class "Default")
      (node (ref "C35L") (pin "40") (pinfunction "40_40") (pintype "passive"))
    )
    (net (code "100") (name "unconnected-(C36L-Pad20)") (class "Default")
      (node (ref "C36L") (pin "20") (pinfunction "20_20") (pintype "passive"))
    )
    (net (code "101") (name "unconnected-(C36L-Pad40)") (class "Default")
      (node (ref "C36L") (pin "40") (pinfunction "40_40") (pintype "passive"))
    )
    (net (code "102") (name "unconnected-(D34L-Pad20)") (class "Default")
      (node (ref "D34L") (pin "20") (pinfunction "20_20") (pintype "passive"))
    )
    (net (code "103") (name "unconnected-(D34L-Pad40)") (class "Default")
      (node (ref "D34L") (pin "40") (pinfunction "40_40") (pintype "passive"))
    )
    (net (code "104") (name "unconnected-(D35L-Pad20)") (class "Default")
      (node (ref "D35L") (pin "20") (pinfunction "20_20") (pintype "passive"))
    )
    (net (code "105") (name "unconnected-(D35L-Pad40)") (class "Default")
      (node (ref "D35L") (pin "40") (pinfunction "40_40") (pintype "passive"))
    )
    (net (code "106") (name "unconnected-(D36L-Pad20)") (class "Default")
      (node (ref "D36L") (pin "20") (pinfunction "20_20") (pintype "passive"))
    )
    (net (code "107") (name "unconnected-(D36L-Pad40)") (class "Default")
      (node (ref "D36L") (pin "40") (pinfunction "40_40") (pintype "passive"))
    )
    (net (code "108") (name "unconnected-(DMA0-3A-BO-Pad13)") (class "Default")
      (node (ref "DMA0-3") (pin "13") (pinfunction "BO_13") (pintype "output"))
    )
    (net (code "109") (name "unconnected-(DMA0-3A-CO-Pad12)") (class "Default")
      (node (ref "DMA0-3") (pin "12") (pinfunction "CO_12") (pintype "output"))
    )
    (net (code "110") (name "unconnected-(DMA4-7A-BO-Pad13)") (class "Default")
      (node (ref "DMA4-7") (pin "13") (pinfunction "BO_13") (pintype "output"))
    )
    (net (code "111") (name "unconnected-(DMA8-11A-BO-Pad13)") (class "Default")
      (node (ref "DMA8-11") (pin "13") (pinfunction "BO_13") (pintype "output"))
    )
    (net (code "112") (name "unconnected-(DMA8-11A-UP-Pad5)") (class "Default")
      (node (ref "DMA8-11") (pin "5") (pinfunction "UP_5") (pintype "input"))
    )
    (net (code "113") (name "unconnected-(EMA4-1A-BO-Pad13)") (class "Default")
      (node (ref "EMA4-1") (pin "13") (pinfunction "BO_13") (pintype "output"))
    )
    (net (code "114") (name "unconnected-(EMA4-1A-CLR-Pad14)") (class "Default")
      (node (ref "EMA4-1") (pin "14") (pinfunction "CLR_14") (pintype "input"))
    )
    (net (code "115") (name "unconnected-(EMA4-1A-CO-Pad12)") (class "Default")
      (node (ref "EMA4-1") (pin "12") (pinfunction "CO_12") (pintype "output"))
    )
    (net (code "116") (name "unconnected-(EMA4-1A-DN-Pad4)") (class "Default")
      (node (ref "EMA4-1") (pin "4") (pinfunction "DN_4") (pintype "input"))
    )
    (net (code "117") (name "unconnected-(EMA4-1A-LD-Pad11)") (class "Default")
      (node (ref "EMA4-1") (pin "11") (pinfunction "LD_11") (pintype "input"))
    )
    (net (code "118") (name "unconnected-(EMA4-1A-UP-Pad5)") (class "Default")
      (node (ref "EMA4-1") (pin "5") (pinfunction "UP_5") (pintype "input"))
    )
    (net (code "119") (name "unconnected-(EMA4-7A-BO-Pad13)") (class "Default")
      (node (ref "EMA4-7") (pin "13") (pinfunction "BO_13") (pintype "output"))
    )
    (net (code "120") (name "unconnected-(EMA4-7A-CLR-Pad14)") (class "Default")
      (node (ref "EMA4-7") (pin "14") (pinfunction "CLR_14") (pintype "input"))
    )
    (net (code "121") (name "unconnected-(EMA4-7A-CO-Pad12)") (class "Default")
      (node (ref "EMA4-7") (pin "12") (pinfunction "CO_12") (pintype "output"))
    )
    (net (code "122") (name "unconnected-(EMA4-7A-DN-Pad4)") (class "Default")
      (node (ref "EMA4-7") (pin "4") (pinfunction "DN_4") (pintype "input"))
    )
    (net (code "123") (name "unconnected-(EMA4-7A-LD-Pad11)") (class "Default")
      (node (ref "EMA4-7") (pin "11") (pinfunction "LD_11") (pintype "input"))
    )
    (net (code "124") (name "unconnected-(EMA4-7A-UP-Pad5)") (class "Default")
      (node (ref "EMA4-7") (pin "5") (pinfunction "UP_5") (pintype "input"))
    )
    (net (code "125") (name "unconnected-(EMA8-11A-BO-Pad13)") (class "Default")
      (node (ref "EMA8-11") (pin "13") (pinfunction "BO_13") (pintype "output"))
    )
    (net (code "126") (name "unconnected-(EMA8-11A-CLR-Pad14)") (class "Default")
      (node (ref "EMA8-11") (pin "14") (pinfunction "CLR_14") (pintype "input"))
    )
    (net (code "127") (name "unconnected-(EMA8-11A-CO-Pad12)") (class "Default")
      (node (ref "EMA8-11") (pin "12") (pinfunction "CO_12") (pintype "output"))
    )
    (net (code "128") (name "unconnected-(EMA8-11A-DN-Pad4)") (class "Default")
      (node (ref "EMA8-11") (pin "4") (pinfunction "DN_4") (pintype "input"))
    )
    (net (code "129") (name "unconnected-(EMA8-11A-LD-Pad11)") (class "Default")
      (node (ref "EMA8-11") (pin "11") (pinfunction "LD_11") (pintype "input"))
    )
    (net (code "130") (name "unconnected-(EMA8-11A-UP-Pad5)") (class "Default")
      (node (ref "EMA8-11") (pin "5") (pinfunction "UP_5") (pintype "input"))
    )
    (net (code "131") (name "unconnected-(IC2A-Y3-Pad12)") (class "Default")
      (node (ref "IC2") (pin "12") (pinfunction "Y3_12") (pintype "output"))
    )
    (net (code "132") (name "unconnected-(IC2A-Y5-Pad10)") (class "Default")
      (node (ref "IC2") (pin "10") (pinfunction "Y5_10") (pintype "output"))
    )
    (net (code "133") (name "unconnected-(IC2A-Y6-Pad9)") (class "Default")
      (node (ref "IC2") (pin "9") (pinfunction "Y6_9") (pintype "output"))
    )
    (net (code "134") (name "unconnected-(IC2A-Y7-Pad7)") (class "Default")
      (node (ref "IC2") (pin "7") (pinfunction "Y7_7") (pintype "output"))
    )
    (net (code "135") (name "unconnected-(IC3A-Y3-Pad12)") (class "Default")
      (node (ref "IC3") (pin "12") (pinfunction "Y3_12") (pintype "output"))
    )
    (net (code "136") (name "unconnected-(IC3A-Y5-Pad10)") (class "Default")
      (node (ref "IC3") (pin "10") (pinfunction "Y5_10") (pintype "output"))
    )
    (net (code "137") (name "unconnected-(IC3A-Y6-Pad9)") (class "Default")
      (node (ref "IC3") (pin "9") (pinfunction "Y6_9") (pintype "output"))
    )
    (net (code "138") (name "unconnected-(IC3A-Y7-Pad7)") (class "Default")
      (node (ref "IC3") (pin "7") (pinfunction "Y7_7") (pintype "output"))
    )
    (net (code "139") (name "unconnected-(IC4A-Y3-Pad12)") (class "Default")
      (node (ref "IC4") (pin "12") (pinfunction "Y3_12") (pintype "output"))
    )
    (net (code "140") (name "unconnected-(IC4A-Y5-Pad10)") (class "Default")
      (node (ref "IC4") (pin "10") (pinfunction "Y5_10") (pintype "output"))
    )
    (net (code "141") (name "unconnected-(IC4A-Y6-Pad9)") (class "Default")
      (node (ref "IC4") (pin "9") (pinfunction "Y6_9") (pintype "output"))
    )
    (net (code "142") (name "unconnected-(IC4A-Y7-Pad7)") (class "Default")
      (node (ref "IC4") (pin "7") (pinfunction "Y7_7") (pintype "output"))
    )
    (net (code "143") (name "~{3CYC}") (class "Default")
      (node (ref "BUS2") (pin "33") (pinfunction "33_33") (pintype "passive"))
      (node (ref "C35L") (pin "28") (pinfunction "28_28") (pintype "passive"))
    )
    (net (code "144") (name "~{601}") (class "Default")
      (node (ref "IC2") (pin "15") (pinfunction "Y0_15") (pintype "output"))
      (node (ref "IC5") (pin "4") (pinfunction "I0_4") (pintype "input"))
      (node (ref "IC5") (pin "5") (pinfunction "I1_5") (pintype "input"))
    )
    (net (code "145") (name "~{602}") (class "Default")
      (node (ref "IC3") (pin "15") (pinfunction "Y0_15") (pintype "output"))
      (node (ref "IC5") (pin "1") (pinfunction "I0_1") (pintype "input"))
    )
    (net (code "146") (name "~{604}") (class "Default")
      (node (ref "IC4") (pin "15") (pinfunction "Y0_15") (pintype "output"))
      (node (ref "IC5") (pin "2") (pinfunction "I1_2") (pintype "input"))
    )
    (net (code "147") (name "~{611}") (class "Default")
      (node (ref "IC2") (pin "14") (pinfunction "Y1_14") (pintype "output"))
    )
    (net (code "148") (name "~{612}") (class "Default")
      (node (ref "IC3") (pin "14") (pinfunction "Y1_14") (pintype "output"))
    )
    (net (code "149") (name "~{614}") (class "Default")
      (node (ref "IC4") (pin "14") (pinfunction "Y1_14") (pintype "output"))
    )
    (net (code "150") (name "~{621}") (class "Default")
      (node (ref "IC2") (pin "13") (pinfunction "Y2_13") (pintype "output"))
    )
    (net (code "151") (name "~{622}") (class "Default")
      (node (ref "IC3") (pin "13") (pinfunction "Y2_13") (pintype "output"))
    )
    (net (code "152") (name "~{624}") (class "Default")
      (node (ref "IC4") (pin "13") (pinfunction "Y2_13") (pintype "output"))
      (node (ref "IC6") (pin "1") (pinfunction "G_1") (pintype "input"))
      (node (ref "IC7") (pin "1") (pinfunction "G_1") (pintype "input"))
      (node (ref "IC8") (pin "1") (pinfunction "G_1") (pintype "input"))
    )
    (net (code "153") (name "~{641}") (class "Default")
      (node (ref "IC2") (pin "11") (pinfunction "Y4_11") (pintype "output"))
    )
    (net (code "154") (name "~{642}") (class "Default")
      (node (ref "IC3") (pin "11") (pinfunction "Y4_11") (pintype "output"))
    )
    (net (code "155") (name "~{644}") (class "Default")
      (node (ref "IC4") (pin "11") (pinfunction "Y4_11") (pintype "output"))
    )
    (net (code "156") (name "~{ACB00}") (class "Default")
      (node (ref "BUS1") (pin "30") (pinfunction "30_30") (pintype "passive"))
      (node (ref "D34L") (pin "2") (pinfunction "2_2") (pintype "passive"))
      (node (ref "IC8") (pin "12") (pinfunction "Y4_12") (pintype "tri_state"))
      (node (ref "IC8") (pin "3") (pinfunction "Y4_3") (pintype "tri_state"))
    )
    (net (code "157") (name "~{ACB01}") (class "Default")
      (node (ref "BUS1") (pin "31") (pinfunction "31_31") (pintype "passive"))
      (node (ref "D34L") (pin "4") (pinfunction "4_4") (pintype "passive"))
      (node (ref "IC8") (pin "14") (pinfunction "Y3_14") (pintype "tri_state"))
      (node (ref "IC8") (pin "5") (pinfunction "Y3_5") (pintype "tri_state"))
    )
    (net (code "158") (name "~{ACB02}") (class "Default")
      (node (ref "BUS1") (pin "32") (pinfunction "32_32") (pintype "passive"))
      (node (ref "D34L") (pin "6") (pinfunction "6_6") (pintype "passive"))
      (node (ref "IC8") (pin "16") (pinfunction "Y2_16") (pintype "tri_state"))
      (node (ref "IC8") (pin "7") (pinfunction "Y2_7") (pintype "tri_state"))
    )
    (net (code "159") (name "~{ACB03}") (class "Default")
      (node (ref "BUS1") (pin "33") (pinfunction "33_33") (pintype "passive"))
      (node (ref "D34L") (pin "8") (pinfunction "8_8") (pintype "passive"))
      (node (ref "IC8") (pin "18") (pinfunction "Y1_18") (pintype "tri_state"))
      (node (ref "IC8") (pin "9") (pinfunction "Y1_9") (pintype "tri_state"))
    )
    (net (code "160") (name "~{ACB04}") (class "Default")
      (node (ref "BUS1") (pin "34") (pinfunction "34_34") (pintype "passive"))
      (node (ref "D34L") (pin "10") (pinfunction "10_10") (pintype "passive"))
      (node (ref "IC7") (pin "12") (pinfunction "Y4_12") (pintype "tri_state"))
      (node (ref "IC7") (pin "3") (pinfunction "Y4_3") (pintype "tri_state"))
    )
    (net (code "161") (name "~{ACB05}") (class "Default")
      (node (ref "BUS1") (pin "35") (pinfunction "35_35") (pintype "passive"))
      (node (ref "D34L") (pin "12") (pinfunction "12_12") (pintype "passive"))
      (node (ref "IC7") (pin "14") (pinfunction "Y3_14") (pintype "tri_state"))
      (node (ref "IC7") (pin "5") (pinfunction "Y3_5") (pintype "tri_state"))
    )
    (net (code "162") (name "~{ACB06}") (class "Default")
      (node (ref "BUS1") (pin "36") (pinfunction "36_36") (pintype "passive"))
      (node (ref "D34L") (pin "14") (pinfunction "14_14") (pintype "passive"))
      (node (ref "IC7") (pin "16") (pinfunction "Y2_16") (pintype "tri_state"))
      (node (ref "IC7") (pin "7") (pinfunction "Y2_7") (pintype "tri_state"))
    )
    (net (code "163") (name "~{ACB07}") (class "Default")
      (node (ref "BUS1") (pin "37") (pinfunction "37_37") (pintype "passive"))
      (node (ref "D34L") (pin "16") (pinfunction "16_16") (pintype "passive"))
      (node (ref "IC7") (pin "18") (pinfunction "Y1_18") (pintype "tri_state"))
      (node (ref "IC7") (pin "9") (pinfunction "Y1_9") (pintype "tri_state"))
    )
    (net (code "164") (name "~{ACB08}") (class "Default")
      (node (ref "BUS1") (pin "38") (pinfunction "38_38") (pintype "passive"))
      (node (ref "D34L") (pin "18") (pinfunction "18_18") (pintype "passive"))
      (node (ref "IC6") (pin "12") (pinfunction "Y4_12") (pintype "tri_state"))
      (node (ref "IC6") (pin "3") (pinfunction "Y4_3") (pintype "tri_state"))
    )
    (net (code "165") (name "~{ACB09}") (class "Default")
      (node (ref "BUS1") (pin "39") (pinfunction "39_39") (pintype "passive"))
      (node (ref "D34L") (pin "22") (pinfunction "22_22") (pintype "passive"))
      (node (ref "IC6") (pin "14") (pinfunction "Y3_14") (pintype "tri_state"))
      (node (ref "IC6") (pin "5") (pinfunction "Y3_5") (pintype "tri_state"))
    )
    (net (code "166") (name "~{ACB10}") (class "Default")
      (node (ref "BUS1") (pin "40") (pinfunction "40_40") (pintype "passive"))
      (node (ref "D34L") (pin "24") (pinfunction "24_24") (pintype "passive"))
      (node (ref "IC6") (pin "16") (pinfunction "Y2_16") (pintype "tri_state"))
      (node (ref "IC6") (pin "7") (pinfunction "Y2_7") (pintype "tri_state"))
    )
    (net (code "167") (name "~{ACB11}") (class "Default")
      (node (ref "BUS2") (pin "1") (pinfunction "1_1") (pintype "passive"))
      (node (ref "D34L") (pin "26") (pinfunction "26_26") (pintype "passive"))
      (node (ref "IC6") (pin "18") (pinfunction "Y1_18") (pintype "tri_state"))
      (node (ref "IC6") (pin "9") (pinfunction "Y1_9") (pintype "tri_state"))
    )
    (net (code "168") (name "~{ACCLEAR}") (class "Default")
      (node (ref "BUS2") (pin "4") (pinfunction "4_4") (pintype "passive"))
      (node (ref "D34L") (pin "32") (pinfunction "32_32") (pintype "passive"))
    )
    (net (code "169") (name "~{BADDAC}") (class "Default")
      (node (ref "BUS2") (pin "20") (pinfunction "20_20") (pintype "passive"))
      (node (ref "C36L") (pin "34") (pinfunction "34_34") (pintype "passive"))
    )
    (net (code "170") (name "~{BBREAK}") (class "Default")
      (node (ref "BUS2") (pin "19") (pinfunction "19_19") (pintype "passive"))
      (node (ref "C36L") (pin "32") (pinfunction "32_32") (pintype "passive"))
    )
    (net (code "171") (name "~{BINIT}") (class "Default")
      (node (ref "C36L") (pin "38") (pinfunction "38_38") (pintype "passive"))
    )
    (net (code "172") (name "~{BMB03}") (class "Default")
      (node (ref "D35L") (pin "8") (pinfunction "8_8") (pintype "passive"))
    )
    (net (code "173") (name "~{BMB04}") (class "Default")
      (node (ref "D35L") (pin "12") (pinfunction "12_12") (pintype "passive"))
    )
    (net (code "174") (name "~{BMB05}") (class "Default")
      (node (ref "D35L") (pin "16") (pinfunction "16_16") (pintype "passive"))
    )
    (net (code "175") (name "~{BMB06}") (class "Default")
      (node (ref "D35L") (pin "22") (pinfunction "22_22") (pintype "passive"))
    )
    (net (code "176") (name "~{BMB07}") (class "Default")
      (node (ref "D35L") (pin "26") (pinfunction "26_26") (pintype "passive"))
    )
    (net (code "177") (name "~{BMB08}") (class "Default")
      (node (ref "D35L") (pin "30") (pinfunction "30_30") (pintype "passive"))
    )
    (net (code "178") (name "~{BRK_RQ}") (class "Default")
      (node (ref "BUS2") (pin "17") (pinfunction "17_17") (pintype "passive"))
      (node (ref "C36L") (pin "28") (pinfunction "28_28") (pintype "passive"))
    )
    (net (code "179") (name "~{BRUN}") (class "Default")
      (node (ref "D34L") (pin "34") (pinfunction "34_34") (pintype "passive"))
    )
    (net (code "180") (name "~{BWCO}") (class "Default")
      (node (ref "BUS2") (pin "34") (pinfunction "34_34") (pintype "passive"))
      (node (ref "C35L") (pin "32") (pinfunction "32_32") (pintype "passive"))
    )
    (net (code "181") (name "~{EXAD0}") (class "Default")
      (node (ref "BUS2") (pin "35") (pinfunction "35_35") (pintype "passive"))
      (node (ref "C35L") (pin "34") (pinfunction "34_34") (pintype "passive"))
    )
    (net (code "182") (name "~{EXAD1}") (class "Default")
      (node (ref "BUS2") (pin "36") (pinfunction "36_36") (pintype "passive"))
      (node (ref "C35L") (pin "36") (pinfunction "36_36") (pintype "passive"))
    )
    (net (code "183") (name "~{EXAD2}") (class "Default")
      (node (ref "BUS2") (pin "37") (pinfunction "37_37") (pintype "passive"))
      (node (ref "C35L") (pin "38") (pinfunction "38_38") (pintype "passive"))
    )
    (net (code "184") (name "~{INT_RQ}") (class "Default")
      (node (ref "BUS2") (pin "3") (pinfunction "3_3") (pintype "passive"))
      (node (ref "D34L") (pin "30") (pinfunction "30_30") (pintype "passive"))
    )
    (net (code "185") (name "~{IOS}") (class "Default")
      (node (ref "BUS2") (pin "2") (pinfunction "2_2") (pintype "passive"))
      (node (ref "D34L") (pin "28") (pinfunction "28_28") (pintype "passive"))
    )
    (net (code "186") (name "~{MYDEV}") (class "Default")
      (node (ref "IC2") (pin "4") (pinfunction "G2A_4") (pintype "input"))
      (node (ref "IC3") (pin "4") (pinfunction "G2A_4") (pintype "input"))
      (node (ref "IC4") (pin "4") (pinfunction "G2A_4") (pintype "input"))
      (node (ref "PAD8") (pin "1") (pinfunction "P_1") (pintype "passive"))
    )
    (net (code "187") (name "~{START}") (class "Default")
      (node (ref "DMA0-3") (pin "11") (pinfunction "LD_11") (pintype "input"))
      (node (ref "DMA4-7") (pin "11") (pinfunction "LD_11") (pintype "input"))
      (node (ref "DMA8-11") (pin "11") (pinfunction "LD_11") (pintype "input"))
      (node (ref "IC5") (pin "3") (pinfunction "O_3") (pintype "output"))
    )
  )
)
